# EDU_High-Speed-Design_CPU_Audio.net
KiCad netlist of a schematic drawn in Altium Designer
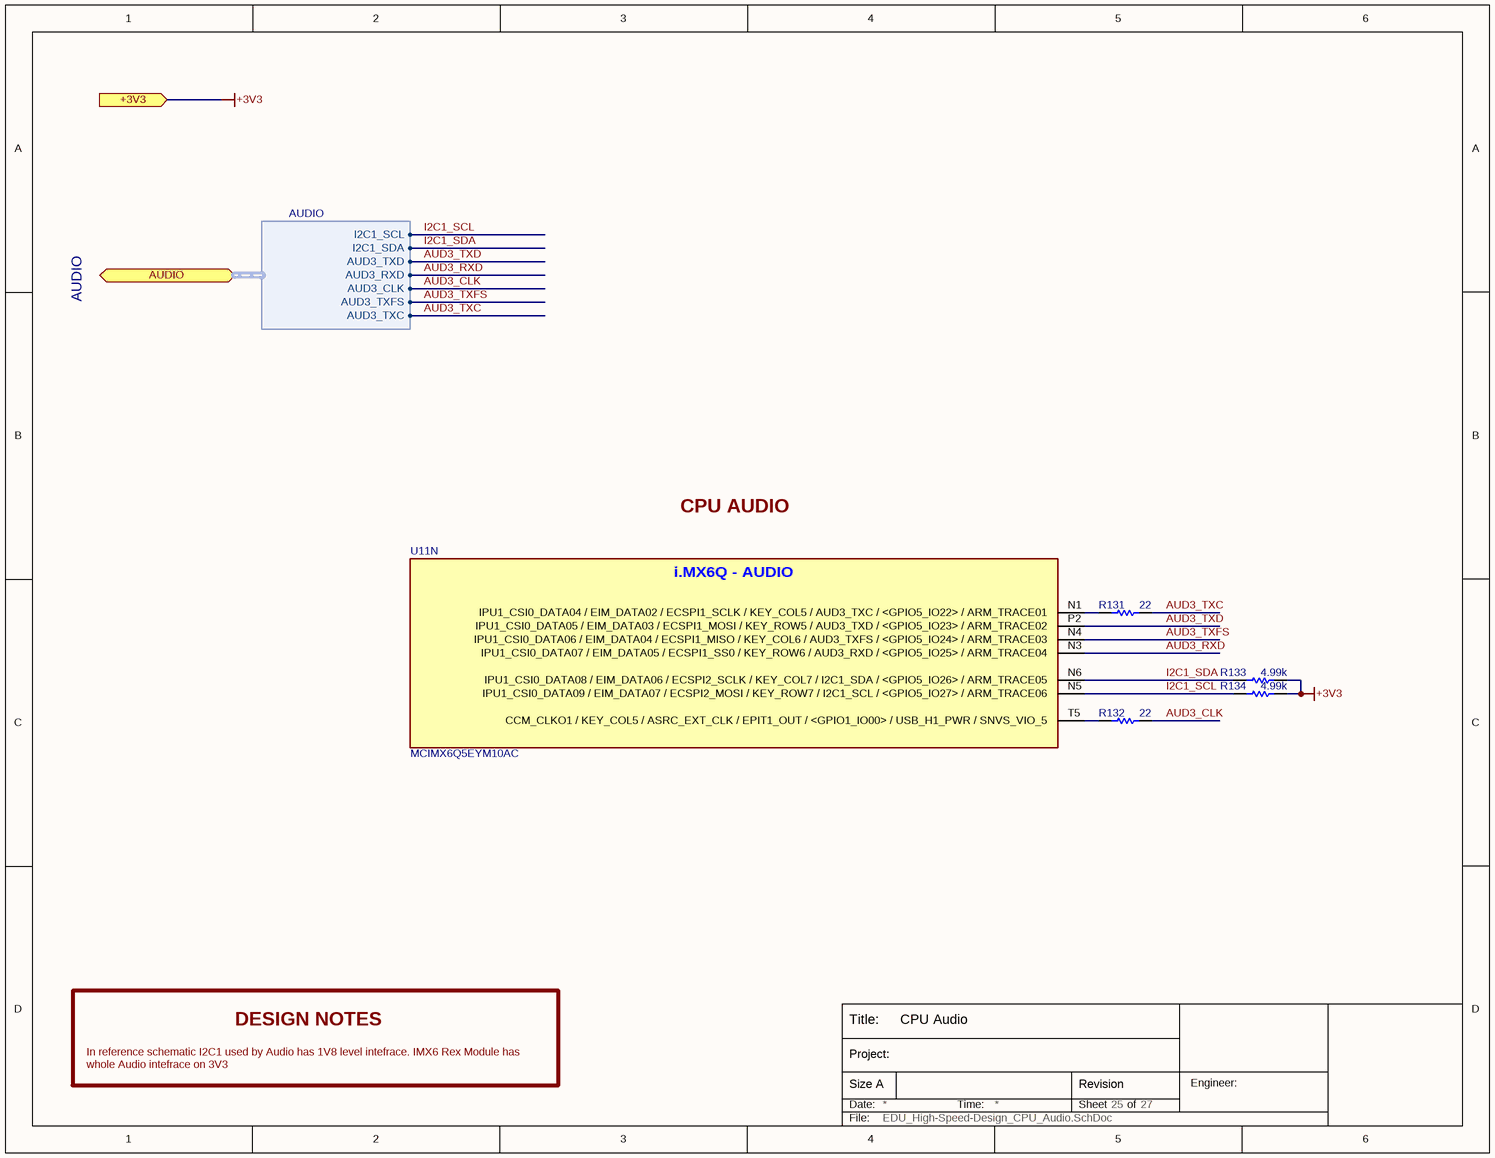
[diagram p0: EDU_High-Speed-Design_CPU_Audio.SchDoc]

(export (version "E")
  (design (tool "Eeschema 10.0.6"))
  (components
    (comp (ref "R131")
      (value "22")
      (footprint "R0402")
      (description "RES 22.0 OHM 1/16W 1% 0402 SMD")
      (libsource (lib "EDU_High-Speed-Design") (part "RC0402FR-0722RL"))
    )
    (comp (ref "R132")
      (value "22")
      (footprint "R0402")
      (description "RES 22.0 OHM 1/16W 1% 0402 SMD")
      (libsource (lib "EDU_High-Speed-Design") (part "RC0402FR-0722RL"))
    )
    (comp (ref "R133")
      (value "4.99k")
      (footprint "R0402")
      (description "RES TF 4.99K OHM 1% 1/16W 0402")
      (libsource (lib "EDU_High-Speed-Design") (part "RMCF0402FT4K99"))
    )
    (comp (ref "R134")
      (value "4.99k")
      (footprint "R0402")
      (description "RES TF 4.99K OHM 1% 1/16W 0402")
      (libsource (lib "EDU_High-Speed-Design") (part "RMCF0402FT4K99"))
    )
    (comp (ref "U11")
      (value "MCIMX6Q5EYM10AC")
      (footprint "MCIMX6Q5EYM10AC")
      (description "IC MCU 32BIT ARM QUAD 624FCBGA")
      (libsource (lib "EDU_High-Speed-Design") (part "MCIMX6Q5EYM10AC"))
    )
  )
  (nets
    (net (code "2") (name "+3V3") (class "Default")
      (node (ref "R133") (pin "2") (pinfunction "2_2") (pintype "passive"))
      (node (ref "R134") (pin "2") (pinfunction "2_2") (pintype "passive"))
    )
    (net (code "3") (name "/AUD3_CLK") (class "Default")
      (node (ref "R132") (pin "1") (pinfunction "1_1") (pintype "passive"))
    )
    (net (code "4") (name "/AUD3_RXD") (class "Default")
      (node (ref "U11") (pin "N3") (pinfunction "IPU1_CSI0_DATA07_/_EIM_DATA05_/_ECSPI1_SS0_/_KEY_ROW6_/_AUD3_RXD_/_<GPIO5_IO25>_/_ARM_TRACE04_N3") (pintype "passive"))
    )
    (net (code "5") (name "/AUD3_TXC") (class "Default")
      (node (ref "R131") (pin "1") (pinfunction "1_1") (pintype "passive"))
    )
    (net (code "6") (name "/AUD3_TXD") (class "Default")
      (node (ref "U11") (pin "P2") (pinfunction "IPU1_CSI0_DATA05_/_EIM_DATA03_/_ECSPI1_MOSI_/_KEY_ROW5_/_AUD3_TXD_/_<GPIO5_IO23>_/_ARM_TRACE02_P2") (pintype "passive"))
    )
    (net (code "7") (name "/AUD3_TXFS") (class "Default")
      (node (ref "U11") (pin "N4") (pinfunction "IPU1_CSI0_DATA06_/_EIM_DATA04_/_ECSPI1_MISO_/_KEY_COL6_/_AUD3_TXFS_/_<GPIO5_IO24>_/_ARM_TRACE03_N4") (pintype "passive"))
    )
    (net (code "8") (name "/I2C1_SCL") (class "Default")
      (node (ref "R134") (pin "1") (pinfunction "1_1") (pintype "passive"))
      (node (ref "U11") (pin "N5") (pinfunction "IPU1_CSI0_DATA09_/_EIM_DATA07_/_ECSPI2_MOSI_/_KEY_ROW7_/_I2C1_SCL_/_<GPIO5_IO27>_/_ARM_TRACE06_N5") (pintype "passive"))
    )
    (net (code "9") (name "/I2C1_SDA") (class "Default")
      (node (ref "R133") (pin "1") (pinfunction "1_1") (pintype "passive"))
      (node (ref "U11") (pin "N6") (pinfunction "IPU1_CSI0_DATA08_/_EIM_DATA06_/_ECSPI2_SCLK_/_KEY_COL7_/_I2C1_SDA_/_<GPIO5_IO26>_/_ARM_TRACE05_N6") (pintype "passive"))
    )
    (net (code "11") (name "Net-(U11N-CCM_CLKO1_{slash}_KEY_COL5_{slash}_ASRC_EXT_CLK_{slash}_EPIT1_OUT_{slash}_<GPIO1_IO00>_{slash}_USB_H1_PWR_{slash}_SNVS_VIO_5)") (class "Default")
      (node (ref "R132") (pin "2") (pinfunction "2_2") (pintype "passive"))
      (node (ref "U11") (pin "T5") (pinfunction "CCM_CLKO1_/_KEY_COL5_/_ASRC_EXT_CLK_/_EPIT1_OUT_/_<GPIO1_IO00>_/_USB_H1_PWR_/_SNVS_VIO_5_T5") (pintype "passive"))
    )
    (net (code "12") (name "Net-(U11N-IPU1_CSI0_DATA04_{slash}_EIM_DATA02_{slash}_ECSPI1_SCLK_{slash}_KEY_COL5_{slash}_AUD3_TXC_{slash}_<GPIO5_IO22>_{slash}_ARM_TRACE01)") (class "Default")
      (node (ref "R131") (pin "2") (pinfunction "2_2") (pintype "passive"))
      (node (ref "U11") (pin "N1") (pinfunction "IPU1_CSI0_DATA04_/_EIM_DATA02_/_ECSPI1_SCLK_/_KEY_COL5_/_AUD3_TXC_/_<GPIO5_IO22>_/_ARM_TRACE01_N1") (pintype "passive"))
    )
  )
)
